# MotorCellTwo.net
KiCad netlist of a schematic drawn in Altium Designer
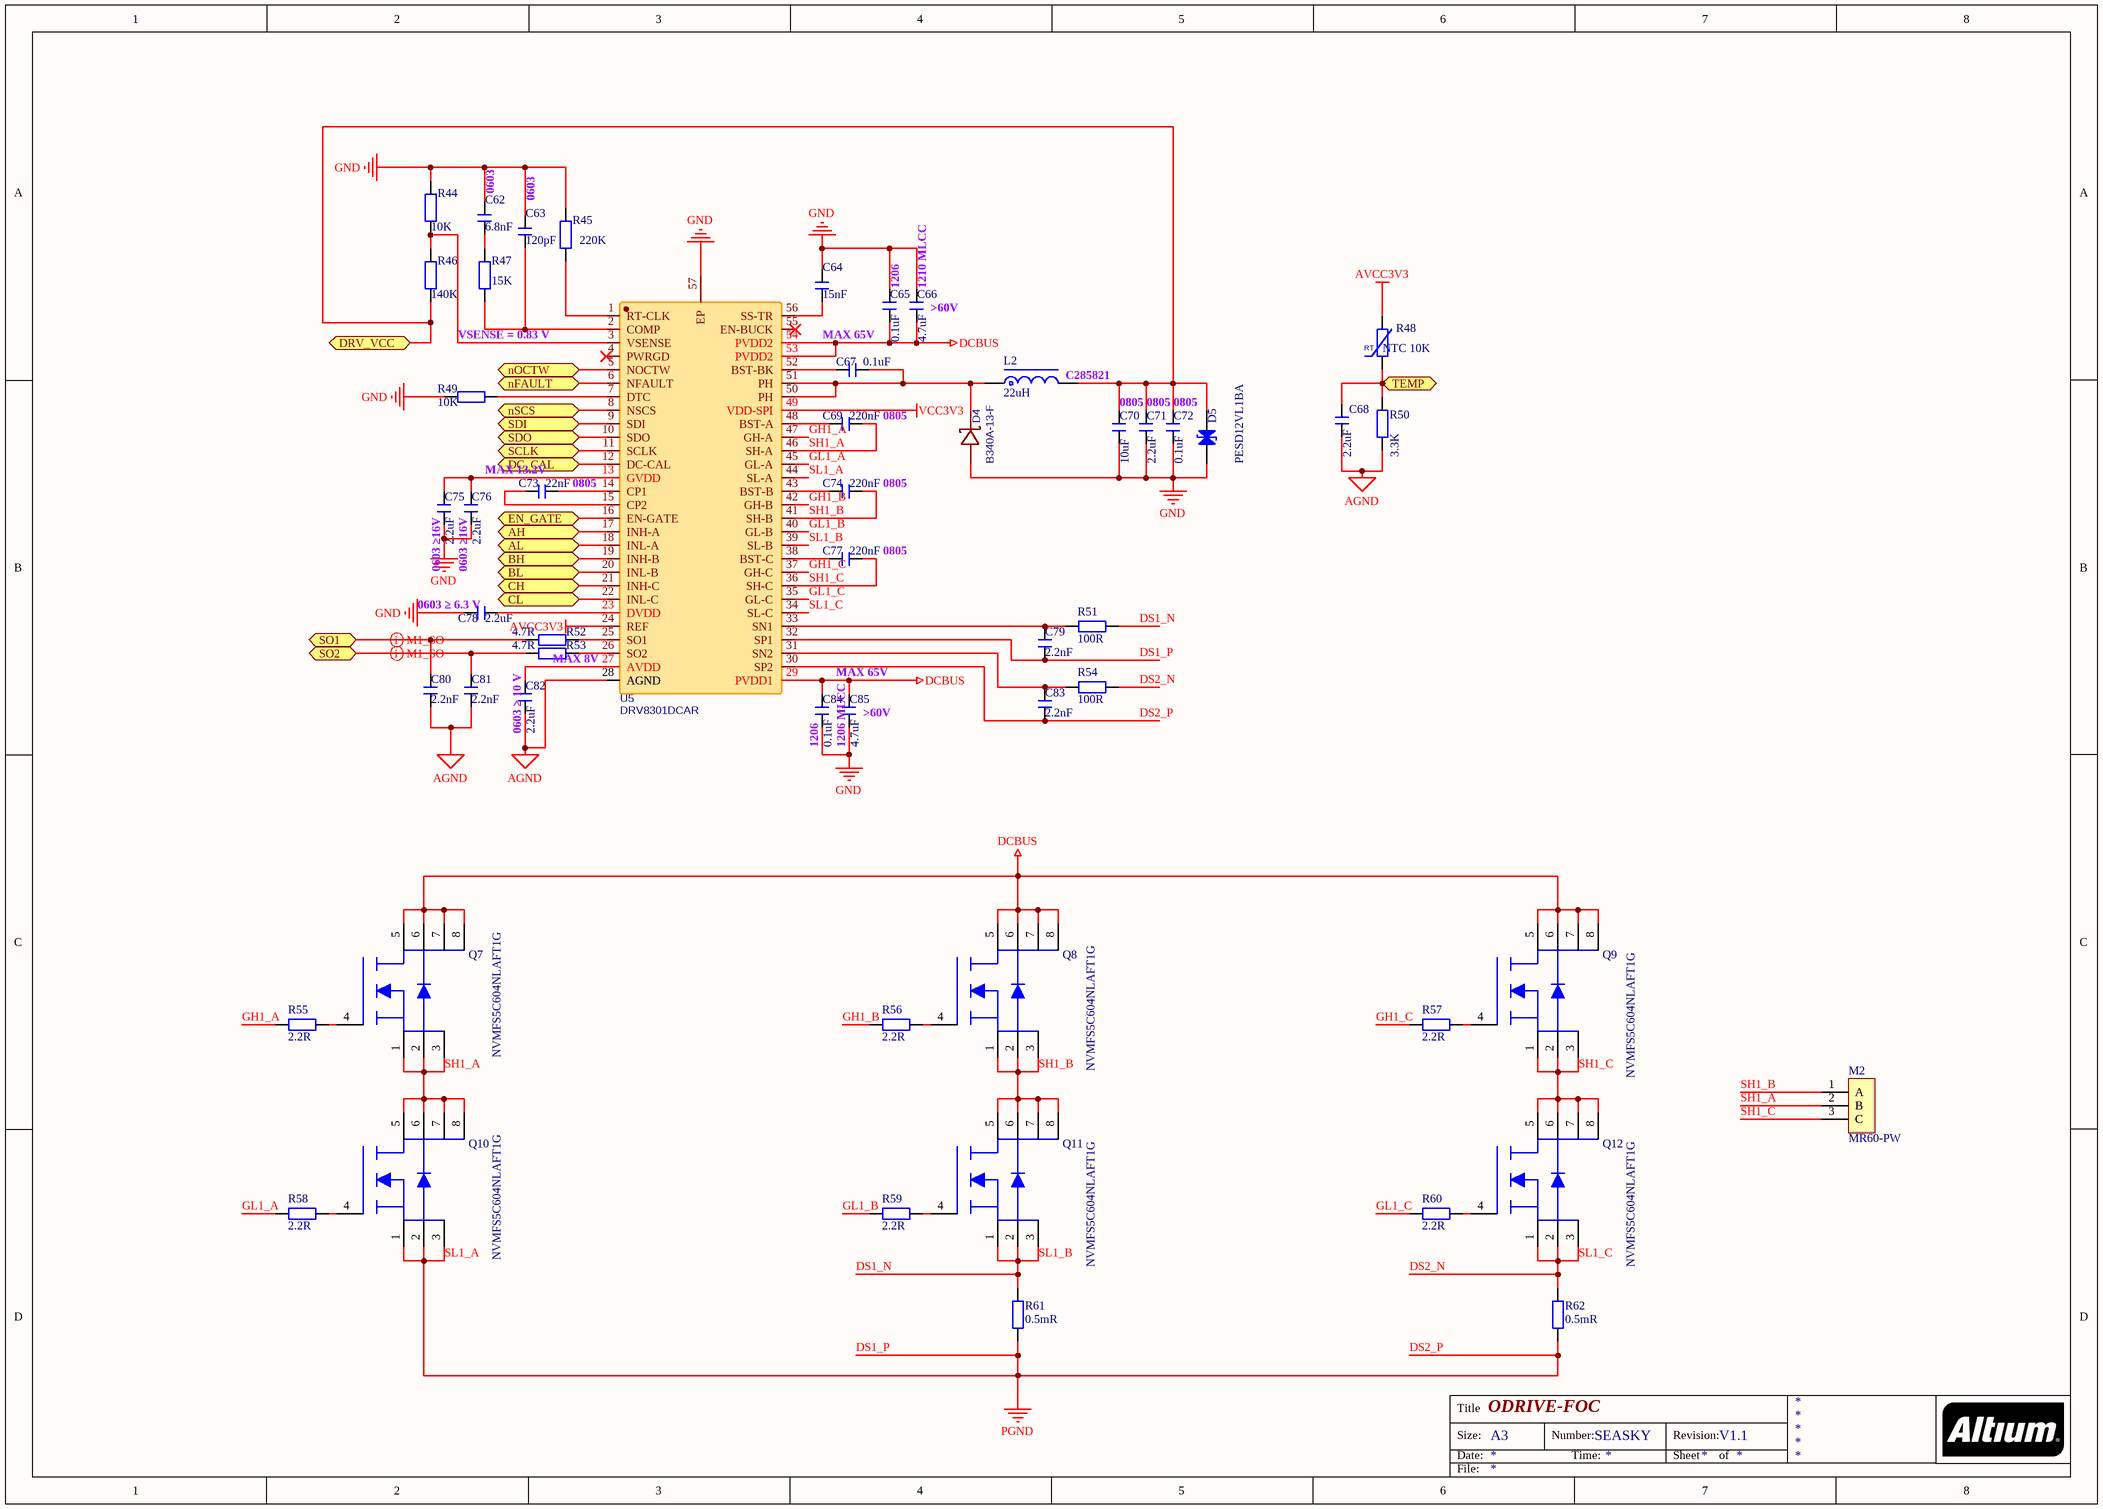
[diagram p0: MotorCellTwo.SchDoc]

(export (version "E")
  (design (tool "Eeschema 10.0.6"))
  (components
    (comp (ref "C62")
      (value "6.8nF")
      (footprint "C 0603_L")
      (description "贴片电容")
      (libsource (lib "0.1 - 电阻-电容-电感") (part "C"))
    )
    (comp (ref "C63")
      (value "120pF")
      (footprint "C 0603_L")
      (description "贴片电容")
      (libsource (lib "0.1 - 电阻-电容-电感") (part "C"))
    )
    (comp (ref "C64")
      (value "15nF")
      (footprint "C 0603_L")
      (description "贴片电容")
      (libsource (lib "0.1 - 电阻-电容-电感") (part "C"))
    )
    (comp (ref "C65")
      (value "0.1uF")
      (footprint "C 1206_L")
      (description "贴片电容")
      (libsource (lib "0.1 - 电阻-电容-电感") (part "C"))
    )
    (comp (ref "C66")
      (value "4.7uF")
      (footprint "C 1210_L")
      (description "贴片电容")
      (libsource (lib "0.1 - 电阻-电容-电感") (part "C"))
    )
    (comp (ref "C67")
      (value "0.1uF")
      (footprint "C 0603_L")
      (description "贴片电容")
      (libsource (lib "0.1 - 电阻-电容-电感") (part "C"))
    )
    (comp (ref "C68")
      (value "2.2uF")
      (footprint "C 0603_L")
      (description "贴片电容")
      (libsource (lib "0.1 - 电阻-电容-电感") (part "C"))
    )
    (comp (ref "C69")
      (value "220nF")
      (footprint "C 0805_L")
      (description "贴片电容")
      (libsource (lib "0.1 - 电阻-电容-电感") (part "C"))
    )
    (comp (ref "C70")
      (value "10uF")
      (footprint "C 0805_L")
      (description "贴片电容")
      (libsource (lib "0.1 - 电阻-电容-电感") (part "C"))
    )
    (comp (ref "C71")
      (value "2.2uF")
      (footprint "C 0805_L")
      (description "贴片电容")
      (libsource (lib "0.1 - 电阻-电容-电感") (part "C"))
    )
    (comp (ref "C72")
      (value "0.1uF")
      (footprint "C 0805_L")
      (description "贴片电容")
      (libsource (lib "0.1 - 电阻-电容-电感") (part "C"))
    )
    (comp (ref "C73")
      (value "22nF")
      (footprint "C 0805_L")
      (description "贴片电容")
      (libsource (lib "0.1 - 电阻-电容-电感") (part "C"))
    )
    (comp (ref "C74")
      (value "220nF")
      (footprint "C 0805_L")
      (description "贴片电容")
      (libsource (lib "0.1 - 电阻-电容-电感") (part "C"))
    )
    (comp (ref "C75")
      (value "2.2uF")
      (footprint "C 0603_L")
      (description "贴片电容")
      (libsource (lib "0.1 - 电阻-电容-电感") (part "C"))
    )
    (comp (ref "C76")
      (value "2.2uF")
      (footprint "C 0603_L")
      (description "贴片电容")
      (libsource (lib "0.1 - 电阻-电容-电感") (part "C"))
    )
    (comp (ref "C77")
      (value "220nF")
      (footprint "C 0805_L")
      (description "贴片电容")
      (libsource (lib "0.1 - 电阻-电容-电感") (part "C"))
    )
    (comp (ref "C78")
      (value "2.2uF")
      (footprint "C 0603_L")
      (description "贴片电容")
      (libsource (lib "0.1 - 电阻-电容-电感") (part "C"))
    )
    (comp (ref "C79")
      (value "2.2nF")
      (footprint "C 0603_L")
      (description "贴片电容")
      (libsource (lib "0.1 - 电阻-电容-电感") (part "C"))
    )
    (comp (ref "C80")
      (value "2.2nF")
      (footprint "C 0603_L")
      (description "贴片电容")
      (libsource (lib "0.1 - 电阻-电容-电感") (part "C"))
    )
    (comp (ref "C81")
      (value "2.2nF")
      (footprint "C 0603_L")
      (description "贴片电容")
      (libsource (lib "0.1 - 电阻-电容-电感") (part "C"))
    )
    (comp (ref "C82")
      (value "2.2uF")
      (footprint "C 0603_L")
      (description "贴片电容")
      (libsource (lib "0.1 - 电阻-电容-电感") (part "C"))
    )
    (comp (ref "C83")
      (value "2.2nF")
      (footprint "C 0603_L")
      (description "贴片电容")
      (libsource (lib "0.1 - 电阻-电容-电感") (part "C"))
    )
    (comp (ref "C84")
      (value "0.1uF")
      (footprint "C 1206_L")
      (description "贴片电容")
      (libsource (lib "0.1 - 电阻-电容-电感") (part "C"))
    )
    (comp (ref "C85")
      (value "4.7uF")
      (footprint "C 1210_L")
      (description "贴片电容")
      (libsource (lib "0.1 - 电阻-电容-电感") (part "C"))
    )
    (comp (ref "D4")
      (value "B340A-13-F")
      (footprint "SMA_L4.4-W2.6-LS5.0-RD")
      (fields (field (name "BOM_SUPPLIER PART") "C85098"))
      (libsource (lib "mx_pcb_library") (part "B340A-13-F"))
    )
    (comp (ref "D5")
      (value "PESD12VL1BA")
      (footprint "SOD-323")
      (description "PESD5V0S1BA、ESD二极管、5V")
      (libsource (lib "0.2 -  二极管-整流桥") (part "PESD5V0S1BA"))
    )
    (comp (ref "L2")
      (value "22uH")
      (footprint "CD53")
      (description "CD系列贴片线绕功率电感")
      (libsource (lib "0.1 - 电阻-电容-电感") (part "L-SMD"))
    )
    (comp (ref "M2")
      (value "MR60-PW")
      (footprint "MR60-PW")
      (libsource (lib "mx_pcb_library") (part "MR60-PW"))
    )
    (comp (ref "Q7")
      (value "NVMFS5C604NLAFT1G")
      (footprint "PG-TDSON-8_L5.0-W6.0-P1.27-LS6.2-BL-EP")
      (libsource (lib "mx_pcb_library") (part "BSC037N08NS5ATMA1"))
    )
    (comp (ref "Q8")
      (value "NVMFS5C604NLAFT1G")
      (footprint "PG-TDSON-8_L5.0-W6.0-P1.27-LS6.2-BL-EP")
      (libsource (lib "mx_pcb_library") (part "BSC037N08NS5ATMA1"))
    )
    (comp (ref "Q9")
      (value "NVMFS5C604NLAFT1G")
      (footprint "PG-TDSON-8_L5.0-W6.0-P1.27-LS6.2-BL-EP")
      (libsource (lib "mx_pcb_library") (part "BSC037N08NS5ATMA1"))
    )
    (comp (ref "Q10")
      (value "NVMFS5C604NLAFT1G")
      (footprint "PG-TDSON-8_L5.0-W6.0-P1.27-LS6.2-BL-EP")
      (libsource (lib "mx_pcb_library") (part "BSC037N08NS5ATMA1"))
    )
    (comp (ref "Q11")
      (value "NVMFS5C604NLAFT1G")
      (footprint "PG-TDSON-8_L5.0-W6.0-P1.27-LS6.2-BL-EP")
      (libsource (lib "mx_pcb_library") (part "BSC037N08NS5ATMA1"))
    )
    (comp (ref "Q12")
      (value "NVMFS5C604NLAFT1G")
      (footprint "PG-TDSON-8_L5.0-W6.0-P1.27-LS6.2-BL-EP")
      (libsource (lib "mx_pcb_library") (part "BSC037N08NS5ATMA1"))
    )
    (comp (ref "R44")
      (value "10K")
      (footprint "R 0603_L")
      (description "贴片电阻")
      (libsource (lib "0.1 - 电阻-电容-电感") (part "R"))
    )
    (comp (ref "R45")
      (value "220K")
      (footprint "R 0603_L")
      (description "贴片电阻")
      (libsource (lib "0.1 - 电阻-电容-电感") (part "R"))
    )
    (comp (ref "R46")
      (value "140K")
      (footprint "R 0603_L")
      (description "贴片电阻")
      (libsource (lib "0.1 - 电阻-电容-电感") (part "R"))
    )
    (comp (ref "R47")
      (value "15K")
      (footprint "R 0603_L")
      (description "贴片电阻")
      (libsource (lib "0.1 - 电阻-电容-电感") (part "R"))
    )
    (comp (ref "R48")
      (value "NTC 10K")
      (footprint "R 0805-HP_L")
      (description "热敏电阻")
      (libsource (lib "0.1 - 电阻-电容-电感") (part "RT"))
    )
    (comp (ref "R49")
      (value "10K")
      (footprint "R 0603_L")
      (description "贴片电阻")
      (libsource (lib "0.1 - 电阻-电容-电感") (part "R"))
    )
    (comp (ref "R50")
      (value "3.3K")
      (footprint "R 0805_L")
      (description "贴片电阻")
      (libsource (lib "0.1 - 电阻-电容-电感") (part "R"))
    )
    (comp (ref "R51")
      (value "100R")
      (footprint "R 0603_L")
      (description "贴片电阻")
      (libsource (lib "0.1 - 电阻-电容-电感") (part "R"))
    )
    (comp (ref "R52")
      (value "4.7R")
      (footprint "R 0603_L")
      (description "贴片电阻")
      (libsource (lib "0.1 - 电阻-电容-电感") (part "R"))
    )
    (comp (ref "R53")
      (value "4.7R")
      (footprint "R 0603_L")
      (description "贴片电阻")
      (libsource (lib "0.1 - 电阻-电容-电感") (part "R"))
    )
    (comp (ref "R54")
      (value "100R")
      (footprint "R 0603_L")
      (description "贴片电阻")
      (libsource (lib "0.1 - 电阻-电容-电感") (part "R"))
    )
    (comp (ref "R55")
      (value "2.2R")
      (footprint "R 0603_L")
      (description "贴片电阻")
      (libsource (lib "0.1 - 电阻-电容-电感") (part "R"))
    )
    (comp (ref "R56")
      (value "2.2R")
      (footprint "R 0603_L")
      (description "贴片电阻")
      (libsource (lib "0.1 - 电阻-电容-电感") (part "R"))
    )
    (comp (ref "R57")
      (value "2.2R")
      (footprint "R 0603_L")
      (description "贴片电阻")
      (libsource (lib "0.1 - 电阻-电容-电感") (part "R"))
    )
    (comp (ref "R58")
      (value "2.2R")
      (footprint "R 0603_L")
      (description "贴片电阻")
      (libsource (lib "0.1 - 电阻-电容-电感") (part "R"))
    )
    (comp (ref "R59")
      (value "2.2R")
      (footprint "R 0603_L")
      (description "贴片电阻")
      (libsource (lib "0.1 - 电阻-电容-电感") (part "R"))
    )
    (comp (ref "R60")
      (value "2.2R")
      (footprint "R 0603_L")
      (description "贴片电阻")
      (libsource (lib "0.1 - 电阻-电容-电感") (part "R"))
    )
    (comp (ref "R61")
      (value "0.5mR")
      (footprint "R3920")
      (description "精密贴片电阻")
      (libsource (lib "0.1 - 电阻-电容-电感") (part "R-Precision"))
    )
    (comp (ref "R62")
      (value "0.5mR")
      (footprint "R3920")
      (description "精密贴片电阻")
      (libsource (lib "0.1 - 电阻-电容-电感") (part "R-Precision"))
    )
    (comp (ref "U5")
      (value "DRV8301DCAR")
      (footprint "HTSSOP-56_L14.0-W6.0-P0.50-LS8.0-BL")
      (fields (field (name "BOM_SUPPLIER PART") "C98969") (field (name "CONTRIBUTOR") "LCSC"))
      (libsource (lib "mx_pcb_library") (part "DRV8301DCAR"))
    )
  )
  (nets
    (net (code "1") (name "/AH") (class "Default")
      (node (ref "U5") (pin "17") (pinfunction "INH-A_17") (pintype "passive"))
    )
    (net (code "2") (name "/AL") (class "Default")
      (node (ref "U5") (pin "18") (pinfunction "INL-A_18") (pintype "passive"))
    )
    (net (code "3") (name "/BH") (class "Default")
      (node (ref "U5") (pin "19") (pinfunction "INH-B_19") (pintype "passive"))
    )
    (net (code "4") (name "/BL") (class "Default")
      (node (ref "U5") (pin "20") (pinfunction "INL-B_20") (pintype "passive"))
    )
    (net (code "5") (name "/CH") (class "Default")
      (node (ref "U5") (pin "21") (pinfunction "INH-C_21") (pintype "passive"))
    )
    (net (code "6") (name "/CL") (class "Default")
      (node (ref "U5") (pin "22") (pinfunction "INL-C_22") (pintype "passive"))
    )
    (net (code "7") (name "/DC_CAL") (class "Default")
      (node (ref "U5") (pin "12") (pinfunction "DC-CAL_12") (pintype "passive"))
    )
    (net (code "8") (name "/DRV_VCC") (class "Default")
      (node (ref "C70") (pin "2") (pinfunction "2_2") (pintype "passive"))
      (node (ref "C71") (pin "2") (pinfunction "2_2") (pintype "passive"))
      (node (ref "C72") (pin "2") (pinfunction "2_2") (pintype "passive"))
      (node (ref "D5") (pin "1") (pinfunction "A_1") (pintype "passive"))
      (node (ref "L2") (pin "2") (pinfunction "2_2") (pintype "passive"))
      (node (ref "R46") (pin "1") (pinfunction "1_1") (pintype "passive"))
    )
    (net (code "9") (name "/DS1_N") (class "Default")
      (node (ref "Q11") (pin "1") (pinfunction "1_1") (pintype "passive"))
      (node (ref "Q11") (pin "2") (pinfunction "2_2") (pintype "passive"))
      (node (ref "Q11") (pin "3") (pinfunction "3_3") (pintype "passive"))
      (node (ref "R51") (pin "2") (pinfunction "2_2") (pintype "passive"))
      (node (ref "R61") (pin "2") (pinfunction "2_2") (pintype "passive"))
      (node (ref "U5") (pin "39") (pinfunction "SL-B_39") (pintype "passive"))
    )
    (net (code "10") (name "/DS2_N") (class "Default")
      (node (ref "Q12") (pin "1") (pinfunction "1_1") (pintype "passive"))
      (node (ref "Q12") (pin "2") (pinfunction "2_2") (pintype "passive"))
      (node (ref "Q12") (pin "3") (pinfunction "3_3") (pintype "passive"))
      (node (ref "R54") (pin "2") (pinfunction "2_2") (pintype "passive"))
      (node (ref "R62") (pin "2") (pinfunction "2_2") (pintype "passive"))
      (node (ref "U5") (pin "34") (pinfunction "SL-C_34") (pintype "passive"))
    )
    (net (code "11") (name "/EN_GATE") (class "Default")
      (node (ref "U5") (pin "16") (pinfunction "EN-GATE_16") (pintype "passive"))
    )
    (net (code "12") (name "/GH1_A") (class "Default")
      (node (ref "R55") (pin "1") (pinfunction "1_1") (pintype "passive"))
      (node (ref "U5") (pin "47") (pinfunction "GH-A_47") (pintype "passive"))
    )
    (net (code "13") (name "/GH1_B") (class "Default")
      (node (ref "R56") (pin "1") (pinfunction "1_1") (pintype "passive"))
      (node (ref "U5") (pin "42") (pinfunction "GH-B_42") (pintype "passive"))
    )
    (net (code "14") (name "/GH1_C") (class "Default")
      (node (ref "R57") (pin "1") (pinfunction "1_1") (pintype "passive"))
      (node (ref "U5") (pin "37") (pinfunction "GH-C_37") (pintype "passive"))
    )
    (net (code "15") (name "/GL1_A") (class "Default")
      (node (ref "R58") (pin "1") (pinfunction "1_1") (pintype "passive"))
      (node (ref "U5") (pin "45") (pinfunction "GL-A_45") (pintype "passive"))
    )
    (net (code "16") (name "/GL1_B") (class "Default")
      (node (ref "R59") (pin "1") (pinfunction "1_1") (pintype "passive"))
      (node (ref "U5") (pin "40") (pinfunction "GL-B_40") (pintype "passive"))
    )
    (net (code "17") (name "/GL1_C") (class "Default")
      (node (ref "R60") (pin "1") (pinfunction "1_1") (pintype "passive"))
      (node (ref "U5") (pin "35") (pinfunction "GL-C_35") (pintype "passive"))
    )
    (net (code "18") (name "/SCLK") (class "Default")
      (node (ref "U5") (pin "11") (pinfunction "SCLK_11") (pintype "passive"))
    )
    (net (code "19") (name "/SDI") (class "Default")
      (node (ref "U5") (pin "9") (pinfunction "SDI_9") (pintype "passive"))
    )
    (net (code "20") (name "/SDO") (class "Default")
      (node (ref "U5") (pin "10") (pinfunction "SDO_10") (pintype "passive"))
    )
    (net (code "21") (name "/SH1_A") (class "Default")
      (node (ref "C69") (pin "2") (pinfunction "2_2") (pintype "passive"))
      (node (ref "M2") (pin "2") (pinfunction "B_2") (pintype "passive"))
      (node (ref "Q10") (pin "5") (pinfunction "5_5") (pintype "passive"))
      (node (ref "Q10") (pin "6") (pinfunction "6_6") (pintype "passive"))
      (node (ref "Q10") (pin "7") (pinfunction "7_7") (pintype "passive"))
      (node (ref "Q10") (pin "8") (pinfunction "8_8") (pintype "passive"))
      (node (ref "Q7") (pin "1") (pinfunction "1_1") (pintype "passive"))
      (node (ref "Q7") (pin "2") (pinfunction "2_2") (pintype "passive"))
      (node (ref "Q7") (pin "3") (pinfunction "3_3") (pintype "passive"))
      (node (ref "U5") (pin "46") (pinfunction "SH-A_46") (pintype "passive"))
    )
    (net (code "22") (name "/SH1_B") (class "Default")
      (node (ref "C74") (pin "2") (pinfunction "2_2") (pintype "passive"))
      (node (ref "M2") (pin "1") (pinfunction "A_1") (pintype "passive"))
      (node (ref "Q11") (pin "5") (pinfunction "5_5") (pintype "passive"))
      (node (ref "Q11") (pin "6") (pinfunction "6_6") (pintype "passive"))
      (node (ref "Q11") (pin "7") (pinfunction "7_7") (pintype "passive"))
      (node (ref "Q11") (pin "8") (pinfunction "8_8") (pintype "passive"))
      (node (ref "Q8") (pin "1") (pinfunction "1_1") (pintype "passive"))
      (node (ref "Q8") (pin "2") (pinfunction "2_2") (pintype "passive"))
      (node (ref "Q8") (pin "3") (pinfunction "3_3") (pintype "passive"))
      (node (ref "U5") (pin "41") (pinfunction "SH-B_41") (pintype "passive"))
    )
    (net (code "23") (name "/SH1_C") (class "Default")
      (node (ref "C77") (pin "2") (pinfunction "2_2") (pintype "passive"))
      (node (ref "M2") (pin "3") (pinfunction "C_3") (pintype "passive"))
      (node (ref "Q12") (pin "5") (pinfunction "5_5") (pintype "passive"))
      (node (ref "Q12") (pin "6") (pinfunction "6_6") (pintype "passive"))
      (node (ref "Q12") (pin "7") (pinfunction "7_7") (pintype "passive"))
      (node (ref "Q12") (pin "8") (pinfunction "8_8") (pintype "passive"))
      (node (ref "Q9") (pin "1") (pinfunction "1_1") (pintype "passive"))
      (node (ref "Q9") (pin "2") (pinfunction "2_2") (pintype "passive"))
      (node (ref "Q9") (pin "3") (pinfunction "3_3") (pintype "passive"))
      (node (ref "U5") (pin "36") (pinfunction "SH-C_36") (pintype "passive"))
    )
    (net (code "24") (name "/SO1") (class "Default")
      (node (ref "C80") (pin "2") (pinfunction "2_2") (pintype "passive"))
      (node (ref "R52") (pin "1") (pinfunction "1_1") (pintype "passive"))
    )
    (net (code "25") (name "/SO2") (class "Default")
      (node (ref "C81") (pin "2") (pinfunction "2_2") (pintype "passive"))
      (node (ref "R53") (pin "1") (pinfunction "1_1") (pintype "passive"))
    )
    (net (code "26") (name "/TEMP") (class "Default")
      (node (ref "C68") (pin "1") (pinfunction "1_1") (pintype "passive"))
      (node (ref "R48") (pin "1") (pinfunction "1_1") (pintype "passive"))
      (node (ref "R50") (pin "2") (pinfunction "2_2") (pintype "passive"))
    )
    (net (code "27") (name "/nFAULT") (class "Default")
      (node (ref "U5") (pin "6") (pinfunction "NFAULT_6") (pintype "passive"))
    )
    (net (code "28") (name "/nOCTW") (class "Default")
      (node (ref "U5") (pin "5") (pinfunction "NOCTW_5") (pintype "passive"))
    )
    (net (code "29") (name "/nSCS") (class "Default")
      (node (ref "U5") (pin "8") (pinfunction "NSCS_8") (pintype "passive"))
    )
    (net (code "30") (name "AGND") (class "Default")
      (node (ref "C68") (pin "2") (pinfunction "2_2") (pintype "passive"))
      (node (ref "C80") (pin "1") (pinfunction "1_1") (pintype "passive"))
      (node (ref "C81") (pin "1") (pinfunction "1_1") (pintype "passive"))
      (node (ref "C82") (pin "1") (pinfunction "1_1") (pintype "passive"))
      (node (ref "R50") (pin "1") (pinfunction "1_1") (pintype "passive"))
      (node (ref "U5") (pin "28") (pinfunction "AGND_28") (pintype "passive"))
    )
    (net (code "31") (name "AVCC3V3") (class "Default")
      (node (ref "R48") (pin "2") (pinfunction "2_2") (pintype "passive"))
      (node (ref "U5") (pin "24") (pinfunction "REF_24") (pintype "passive"))
    )
    (net (code "32") (name "DCBUS") (class "Default")
      (node (ref "C65") (pin "1") (pinfunction "1_1") (pintype "passive"))
      (node (ref "C66") (pin "1") (pinfunction "1_1") (pintype "passive"))
      (node (ref "C84") (pin "2") (pinfunction "2_2") (pintype "passive"))
      (node (ref "C85") (pin "2") (pinfunction "2_2") (pintype "passive"))
      (node (ref "Q7") (pin "5") (pinfunction "5_5") (pintype "passive"))
      (node (ref "Q7") (pin "6") (pinfunction "6_6") (pintype "passive"))
      (node (ref "Q7") (pin "7") (pinfunction "7_7") (pintype "passive"))
      (node (ref "Q7") (pin "8") (pinfunction "8_8") (pintype "passive"))
      (node (ref "Q8") (pin "5") (pinfunction "5_5") (pintype "passive"))
      (node (ref "Q8") (pin "6") (pinfunction "6_6") (pintype "passive"))
      (node (ref "Q8") (pin "7") (pinfunction "7_7") (pintype "passive"))
      (node (ref "Q8") (pin "8") (pinfunction "8_8") (pintype "passive"))
      (node (ref "Q9") (pin "5") (pinfunction "5_5") (pintype "passive"))
      (node (ref "Q9") (pin "6") (pinfunction "6_6") (pintype "passive"))
      (node (ref "Q9") (pin "7") (pinfunction "7_7") (pintype "passive"))
      (node (ref "Q9") (pin "8") (pinfunction "8_8") (pintype "passive"))
      (node (ref "U5") (pin "29") (pinfunction "PVDD1_29") (pintype "passive"))
      (node (ref "U5") (pin "53") (pinfunction "PVDD2_53") (pintype "passive"))
      (node (ref "U5") (pin "54") (pinfunction "PVDD2_54") (pintype "passive"))
    )
    (net (code "33") (name "GND") (class "Default")
      (node (ref "C62") (pin "1") (pinfunction "1_1") (pintype "passive"))
      (node (ref "C63") (pin "1") (pinfunction "1_1") (pintype "passive"))
      (node (ref "C64") (pin "1") (pinfunction "1_1") (pintype "passive"))
      (node (ref "C65") (pin "2") (pinfunction "2_2") (pintype "passive"))
      (node (ref "C66") (pin "2") (pinfunction "2_2") (pintype "passive"))
      (node (ref "C70") (pin "1") (pinfunction "1_1") (pintype "passive"))
      (node (ref "C71") (pin "1") (pinfunction "1_1") (pintype "passive"))
      (node (ref "C72") (pin "1") (pinfunction "1_1") (pintype "passive"))
      (node (ref "C75") (pin "1") (pinfunction "1_1") (pintype "passive"))
      (node (ref "C76") (pin "1") (pinfunction "1_1") (pintype "passive"))
      (node (ref "C78") (pin "1") (pinfunction "1_1") (pintype "passive"))
      (node (ref "C84") (pin "1") (pinfunction "1_1") (pintype "passive"))
      (node (ref "C85") (pin "1") (pinfunction "1_1") (pintype "passive"))
      (node (ref "D4") (pin "2") (pinfunction "A_2") (pintype "passive"))
      (node (ref "D5") (pin "2") (pinfunction "K_2") (pintype "passive"))
      (node (ref "R44") (pin "2") (pinfunction "2_2") (pintype "passive"))
      (node (ref "R45") (pin "2") (pinfunction "2_2") (pintype "passive"))
      (node (ref "R49") (pin "2") (pinfunction "2_2") (pintype "passive"))
      (node (ref "U5") (pin "57") (pinfunction "EP_57") (pintype "passive"))
    )
    (net (code "34") (name "Net-(C62-Pad2)") (class "Default")
      (node (ref "C62") (pin "2") (pinfunction "2_2") (pintype "passive"))
      (node (ref "R47") (pin "2") (pinfunction "2_2") (pintype "passive"))
    )
    (net (code "35") (name "Net-(D4-K)") (class "Default")
      (node (ref "C67") (pin "1") (pinfunction "1_1") (pintype "passive"))
      (node (ref "D4") (pin "1") (pinfunction "K_1") (pintype "passive"))
      (node (ref "L2") (pin "1") (pinfunction "1_1") (pintype "passive"))
      (node (ref "U5") (pin "50") (pinfunction "PH_50") (pintype "passive"))
      (node (ref "U5") (pin "51") (pinfunction "PH_51") (pintype "passive"))
    )
    (net (code "36") (name "Net-(Q7-Pad4)") (class "Default")
      (node (ref "Q7") (pin "4") (pinfunction "4_4") (pintype "passive"))
      (node (ref "R55") (pin "2") (pinfunction "2_2") (pintype "passive"))
    )
    (net (code "37") (name "Net-(Q8-Pad4)") (class "Default")
      (node (ref "Q8") (pin "4") (pinfunction "4_4") (pintype "passive"))
      (node (ref "R56") (pin "2") (pinfunction "2_2") (pintype "passive"))
    )
    (net (code "38") (name "Net-(Q9-Pad4)") (class "Default")
      (node (ref "Q9") (pin "4") (pinfunction "4_4") (pintype "passive"))
      (node (ref "R57") (pin "2") (pinfunction "2_2") (pintype "passive"))
    )
    (net (code "39") (name "Net-(Q10-Pad4)") (class "Default")
      (node (ref "Q10") (pin "4") (pinfunction "4_4") (pintype "passive"))
      (node (ref "R58") (pin "2") (pinfunction "2_2") (pintype "passive"))
    )
    (net (code "40") (name "Net-(Q11-Pad4)") (class "Default")
      (node (ref "Q11") (pin "4") (pinfunction "4_4") (pintype "passive"))
      (node (ref "R59") (pin "2") (pinfunction "2_2") (pintype "passive"))
    )
    (net (code "41") (name "Net-(Q12-Pad4)") (class "Default")
      (node (ref "Q12") (pin "4") (pinfunction "4_4") (pintype "passive"))
      (node (ref "R60") (pin "2") (pinfunction "2_2") (pintype "passive"))
    )
    (net (code "42") (name "Net-(U5-AVDD)") (class "Default")
      (node (ref "C82") (pin "2") (pinfunction "2_2") (pintype "passive"))
      (node (ref "U5") (pin "27") (pinfunction "AVDD_27") (pintype "passive"))
    )
    (net (code "43") (name "Net-(U5-BST-A)") (class "Default")
      (node (ref "C69") (pin "1") (pinfunction "1_1") (pintype "passive"))
      (node (ref "U5") (pin "48") (pinfunction "BST-A_48") (pintype "passive"))
    )
    (net (code "44") (name "Net-(U5-BST-B)") (class "Default")
      (node (ref "C74") (pin "1") (pinfunction "1_1") (pintype "passive"))
      (node (ref "U5") (pin "43") (pinfunction "BST-B_43") (pintype "passive"))
    )
    (net (code "45") (name "Net-(U5-BST-BK)") (class "Default")
      (node (ref "C67") (pin "2") (pinfunction "2_2") (pintype "passive"))
      (node (ref "U5") (pin "52") (pinfunction "BST-BK_52") (pintype "passive"))
    )
    (net (code "46") (name "Net-(U5-BST-C)") (class "Default")
      (node (ref "C77") (pin "1") (pinfunction "1_1") (pintype "passive"))
      (node (ref "U5") (pin "38") (pinfunction "BST-C_38") (pintype "passive"))
    )
    (net (code "47") (name "Net-(U5-COMP)") (class "Default")
      (node (ref "C63") (pin "2") (pinfunction "2_2") (pintype "passive"))
      (node (ref "R47") (pin "1") (pinfunction "1_1") (pintype "passive"))
      (node (ref "U5") (pin "2") (pinfunction "COMP_2") (pintype "passive"))
    )
    (net (code "48") (name "Net-(U5-CP1)") (class "Default")
      (node (ref "C73") (pin "1") (pinfunction "1_1") (pintype "passive"))
      (node (ref "U5") (pin "14") (pinfunction "CP1_14") (pintype "passive"))
    )
    (net (code "49") (name "Net-(U5-CP2)") (class "Default")
      (node (ref "C73") (pin "2") (pinfunction "2_2") (pintype "passive"))
      (node (ref "U5") (pin "15") (pinfunction "CP2_15") (pintype "passive"))
    )
    (net (code "50") (name "Net-(U5-DTC)") (class "Default")
      (node (ref "R49") (pin "1") (pinfunction "1_1") (pintype "passive"))
      (node (ref "U5") (pin "7") (pinfunction "DTC_7") (pintype "passive"))
    )
    (net (code "51") (name "Net-(U5-DVDD)") (class "Default")
      (node (ref "C78") (pin "2") (pinfunction "2_2") (pintype "passive"))
      (node (ref "U5") (pin "23") (pinfunction "DVDD_23") (pintype "passive"))
    )
    (net (code "52") (name "Net-(U5-GVDD)") (class "Default")
      (node (ref "C75") (pin "2") (pinfunction "2_2") (pintype "passive"))
      (node (ref "C76") (pin "2") (pinfunction "2_2") (pintype "passive"))
      (node (ref "U5") (pin "13") (pinfunction "GVDD_13") (pintype "passive"))
    )
    (net (code "53") (name "Net-(U5-RT-CLK)") (class "Default")
      (node (ref "R45") (pin "1") (pinfunction "1_1") (pintype "passive"))
      (node (ref "U5") (pin "1") (pinfunction "RT-CLK_1") (pintype "passive"))
    )
    (net (code "54") (name "Net-(U5-SN1)") (class "Default")
      (node (ref "C79") (pin "2") (pinfunction "2_2") (pintype "passive"))
      (node (ref "R51") (pin "1") (pinfunction "1_1") (pintype "passive"))
      (node (ref "U5") (pin "33") (pinfunction "SN1_33") (pintype "passive"))
    )
    (net (code "55") (name "Net-(U5-SN2)") (class "Default")
      (node (ref "C83") (pin "2") (pinfunction "2_2") (pintype "passive"))
      (node (ref "R54") (pin "1") (pinfunction "1_1") (pintype "passive"))
      (node (ref "U5") (pin "31") (pinfunction "SN2_31") (pintype "passive"))
    )
    (net (code "56") (name "Net-(U5-SO1)") (class "Default")
      (node (ref "R52") (pin "2") (pinfunction "2_2") (pintype "passive"))
      (node (ref "U5") (pin "25") (pinfunction "SO1_25") (pintype "passive"))
    )
    (net (code "57") (name "Net-(U5-SO2)") (class "Default")
      (node (ref "R53") (pin "2") (pinfunction "2_2") (pintype "passive"))
      (node (ref "U5") (pin "26") (pinfunction "SO2_26") (pintype "passive"))
    )
    (net (code "58") (name "Net-(U5-SS-TR)") (class "Default")
      (node (ref "C64") (pin "2") (pinfunction "2_2") (pintype "passive"))
      (node (ref "U5") (pin "56") (pinfunction "SS-TR_56") (pintype "passive"))
    )
    (net (code "59") (name "Net-(U5-VSENSE)") (class "Default")
      (node (ref "R44") (pin "1") (pinfunction "1_1") (pintype "passive"))
      (node (ref "R46") (pin "2") (pinfunction "2_2") (pintype "passive"))
      (node (ref "U5") (pin "3") (pinfunction "VSENSE_3") (pintype "passive"))
    )
    (net (code "60") (name "PGND") (class "Default")
      (node (ref "C79") (pin "1") (pinfunction "1_1") (pintype "passive"))
      (node (ref "C83") (pin "1") (pinfunction "1_1") (pintype "passive"))
      (node (ref "Q10") (pin "1") (pinfunction "1_1") (pintype "passive"))
      (node (ref "Q10") (pin "2") (pinfunction "2_2") (pintype "passive"))
      (node (ref "Q10") (pin "3") (pinfunction "3_3") (pintype "passive"))
      (node (ref "R61") (pin "1") (pinfunction "1_1") (pintype "passive"))
      (node (ref "R62") (pin "1") (pinfunction "1_1") (pintype "passive"))
      (node (ref "U5") (pin "30") (pinfunction "SP2_30") (pintype "passive"))
      (node (ref "U5") (pin "32") (pinfunction "SP1_32") (pintype "passive"))
      (node (ref "U5") (pin "44") (pinfunction "SL-A_44") (pintype "passive"))
    )
    (net (code "61") (name "VCC3V3") (class "Default")
      (node (ref "U5") (pin "49") (pinfunction "VDD-SPI_49") (pintype "passive"))
    )
    (net (code "62") (name "unconnected-(U5-EN-BUCK-Pad55)") (class "Default")
      (node (ref "U5") (pin "55") (pinfunction "EN-BUCK_55") (pintype "passive+no_connect"))
    )
    (net (code "63") (name "unconnected-(U5-PWRGD-Pad4)") (class "Default")
      (node (ref "U5") (pin "4") (pinfunction "PWRGD_4") (pintype "passive+no_connect"))
    )
  )
)
